# sch.net
KiCad netlist of a schematic drawn in EasyEDA
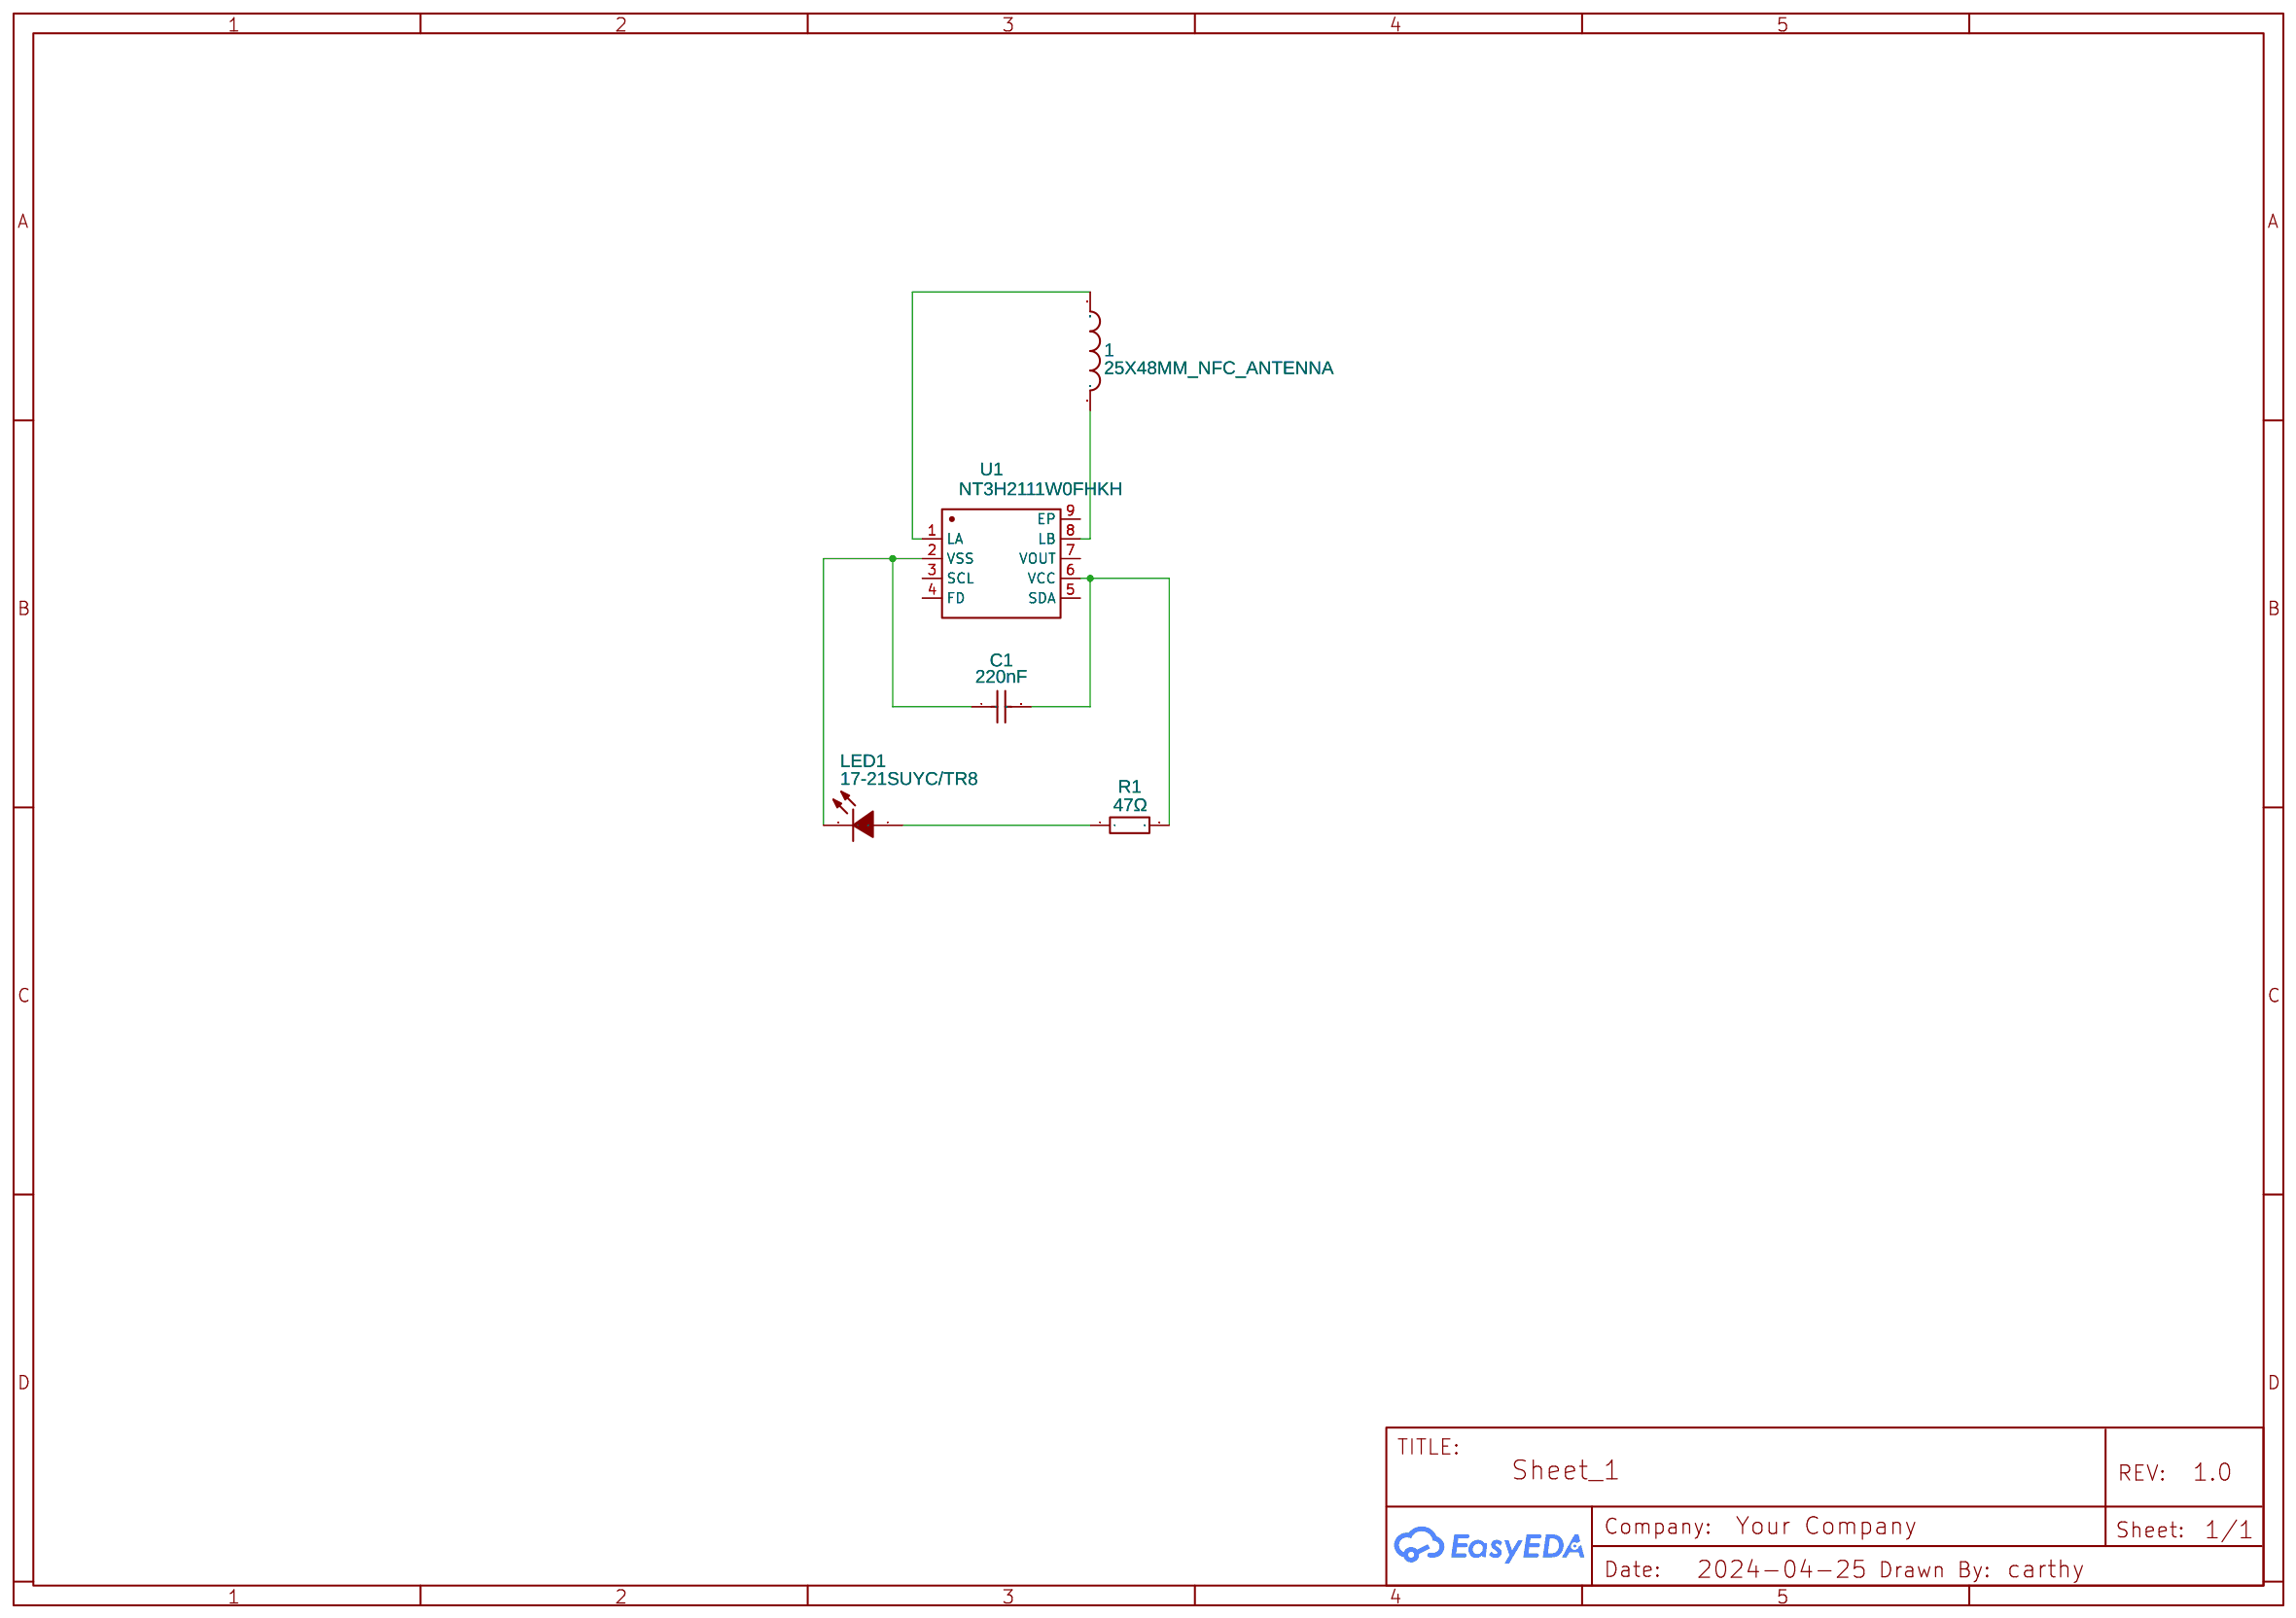
[diagram p0: schematic sheet]

(export (version "E")
  (design (tool "Eeschema 10.0.6"))
  (components
    (comp (ref "1") (value "25X48MM_NFC_ANTENNA") (libsource (lib "") (part "25X48MM_NFC_ANTENNA")))
    (comp (ref "C1")
      (value "220nF")
      (fields
        (field (name "Manufacturer Part") "CL10B224KA8NNNC")
        (field (name "Manufacturer") "SAMSUNG(三星)")
      )
      (libsource (lib "") (part "CL10B224KA8NNNC"))
    )
    (comp (ref "LED1")
      (value "17-21SUYC/TR8")
      (fields (field (name "Manufacturer Part") "KT-0805黄灯") (field (name "Manufacturer") "KENTO"))
      (libsource (lib "") (part "17-21SUYC/TR8"))
    )
    (comp (ref "R1")
      (value "47Ω")
      (fields
        (field (name "Manufacturer Part") "0603WAF470JT5E")
        (field (name "Manufacturer") "UNI-ROYAL(厚声)")
      )
      (libsource (lib "") (part "0603WAF470JT5E"))
    )
    (comp (ref "U1")
      (value "NT3H2111W0FHKH")
      (fields (field (name "Manufacturer") "NXP(恩智浦)"))
      (libsource (lib "") (part "NT3H2111W0FHKH"))
    )
  )
  (nets
    (net (code "1") (name "Net-(LED1-+)") (class "Default")
      (node (ref "LED1") (pin "1") (pinfunction "+_1") (pintype "unspecified"))
      (node (ref "R1") (pin "1") (pinfunction "1_1") (pintype "input"))
    )
    (net (code "2") (name "Net-(LED1--)") (class "Default")
      (node (ref "C1") (pin "1") (pinfunction "1_1") (pintype "input"))
      (node (ref "LED1") (pin "2") (pinfunction "-_2") (pintype "unspecified"))
      (node (ref "U1") (pin "2") (pinfunction "VSS_2") (pintype "unspecified"))
    )
    (net (code "3") (name "Net-(U1-LA)") (class "Default")
      (node (ref "1") (pin "P$1") (pinfunction "P$1_P$1") (pintype "bidirectional"))
      (node (ref "U1") (pin "1") (pinfunction "LA_1") (pintype "unspecified"))
    )
    (net (code "4") (name "Net-(U1-LB)") (class "Default")
      (node (ref "1") (pin "P$2") (pinfunction "P$2_P$2") (pintype "bidirectional"))
      (node (ref "U1") (pin "8") (pinfunction "LB_8") (pintype "unspecified"))
    )
    (net (code "5") (name "Net-(U1-VCC)") (class "Default")
      (node (ref "C1") (pin "2") (pinfunction "2_2") (pintype "input"))
      (node (ref "R1") (pin "2") (pinfunction "2_2") (pintype "input"))
      (node (ref "U1") (pin "6") (pinfunction "VCC_6") (pintype "unspecified"))
    )
    (net (code "6") (name "unconnected-(U1-EP-Pad9)") (class "Default")
      (node (ref "U1") (pin "9") (pinfunction "EP_9") (pintype "unspecified"))
    )
    (net (code "7") (name "unconnected-(U1-FD-Pad4)") (class "Default")
      (node (ref "U1") (pin "4") (pinfunction "FD_4") (pintype "unspecified"))
    )
    (net (code "8") (name "unconnected-(U1-SCL-Pad3)") (class "Default")
      (node (ref "U1") (pin "3") (pinfunction "SCL_3") (pintype "unspecified"))
    )
    (net (code "9") (name "unconnected-(U1-SDA-Pad5)") (class "Default")
      (node (ref "U1") (pin "5") (pinfunction "SDA_5") (pintype "unspecified"))
    )
    (net (code "10") (name "unconnected-(U1-VOUT-Pad7)") (class "Default")
      (node (ref "U1") (pin "7") (pinfunction "VOUT_7") (pintype "unspecified"))
    )
  )
)
